# Centinel_IO_adap.net
KiCad netlist of a schematic drawn in EAGLE
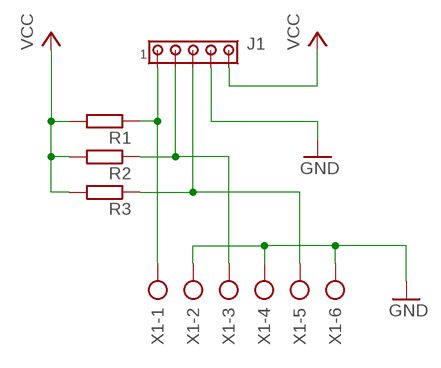
[diagram p0: schematic, sheet 1]

(export (version "E")
  (design (tool "Eeschema 10.0.6"))
  (components
    (comp (ref "J1")
      (value "MTA05-156")
      (footprint "eagle-import:1X5MTA")
      (libsource (lib "eagle-import") (part "MTA05-156"))
    )
    (comp (ref "R1")
      (value "R-EU_0207/7")
      (footprint "eagle-import:0207_7")
      (libsource (lib "eagle-import") (part "R-EU_0207/7"))
    )
    (comp (ref "R2")
      (value "R-EU_0207/7")
      (footprint "eagle-import:0207_7")
      (libsource (lib "eagle-import") (part "R-EU_0207/7"))
    )
    (comp (ref "R3")
      (value "R-EU_0207/7")
      (footprint "eagle-import:0207_7")
      (libsource (lib "eagle-import") (part "R-EU_0207/7"))
    )
    (comp (ref "X1")
      (value "AK500/6")
      (footprint "eagle-import:AK500_6")
      (libsource (lib "eagle-import") (part "AK500/6"))
    )
  )
  (nets
    (net (code "1") (name "GND") (class "Default")
      (node (ref "J1") (pin "4") (pinfunction "4_4") (pintype "passive"))
      (node (ref "X1") (pin "2") (pinfunction "KL_2") (pintype "passive"))
      (node (ref "X1") (pin "4") (pinfunction "KL_4") (pintype "passive"))
      (node (ref "X1") (pin "6") (pinfunction "KL_6") (pintype "passive"))
    )
    (net (code "2") (name "Net-(X1A-KL)") (class "Default")
      (node (ref "J1") (pin "1") (pinfunction "1_1") (pintype "passive"))
      (node (ref "R1") (pin "1") (pinfunction "1_1") (pintype "passive"))
      (node (ref "X1") (pin "1") (pinfunction "KL_1") (pintype "passive"))
    )
    (net (code "3") (name "Net-(X1C-KL)") (class "Default")
      (node (ref "J1") (pin "2") (pinfunction "2_2") (pintype "passive"))
      (node (ref "R2") (pin "1") (pinfunction "1_1") (pintype "passive"))
      (node (ref "X1") (pin "3") (pinfunction "KL_3") (pintype "passive"))
    )
    (net (code "4") (name "Net-(X1E-KL)") (class "Default")
      (node (ref "J1") (pin "3") (pinfunction "3_3") (pintype "passive"))
      (node (ref "R3") (pin "1") (pinfunction "1_1") (pintype "passive"))
      (node (ref "X1") (pin "5") (pinfunction "KL_5") (pintype "passive"))
    )
    (net (code "5") (name "VCC") (class "Default")
      (node (ref "J1") (pin "5") (pinfunction "5_5") (pintype "passive"))
      (node (ref "R1") (pin "2") (pinfunction "2_2") (pintype "passive"))
      (node (ref "R2") (pin "2") (pinfunction "2_2") (pintype "passive"))
      (node (ref "R3") (pin "2") (pinfunction "2_2") (pintype "passive"))
    )
  )
)
